# YuriPre2_0.net
KiCad netlist of a schematic drawn in EasyEDA Pro
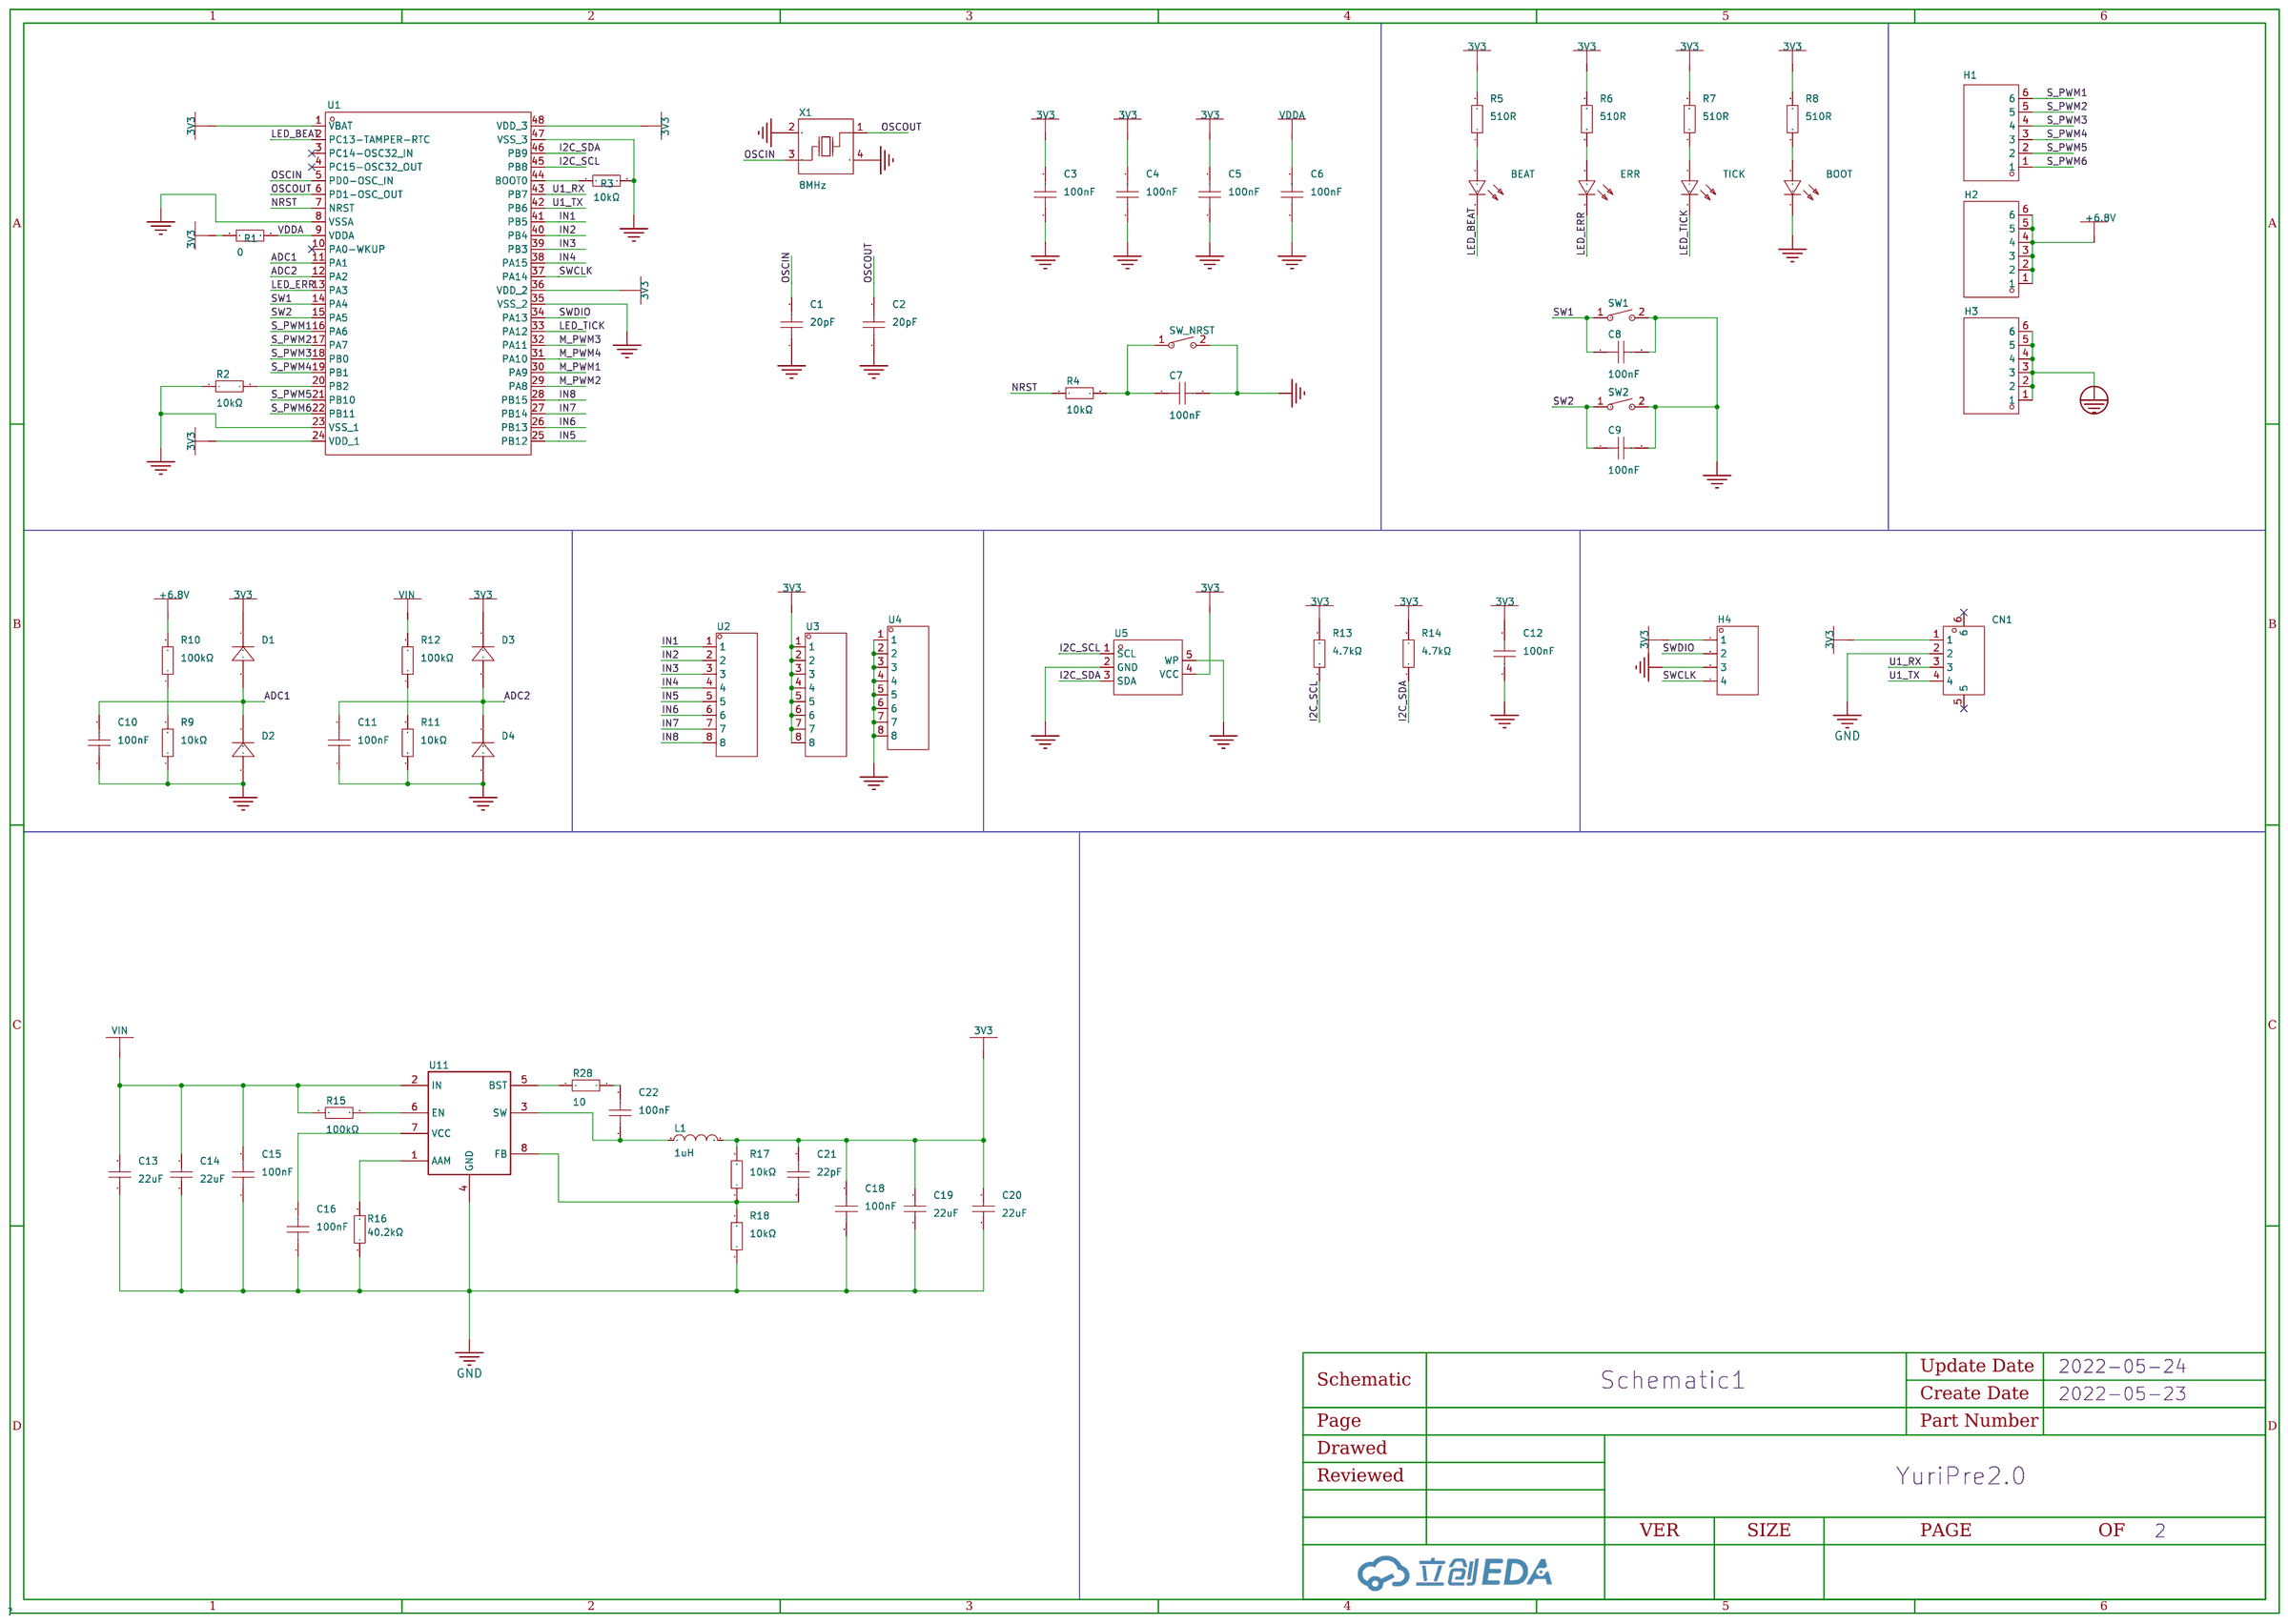
[diagram p0: P1]
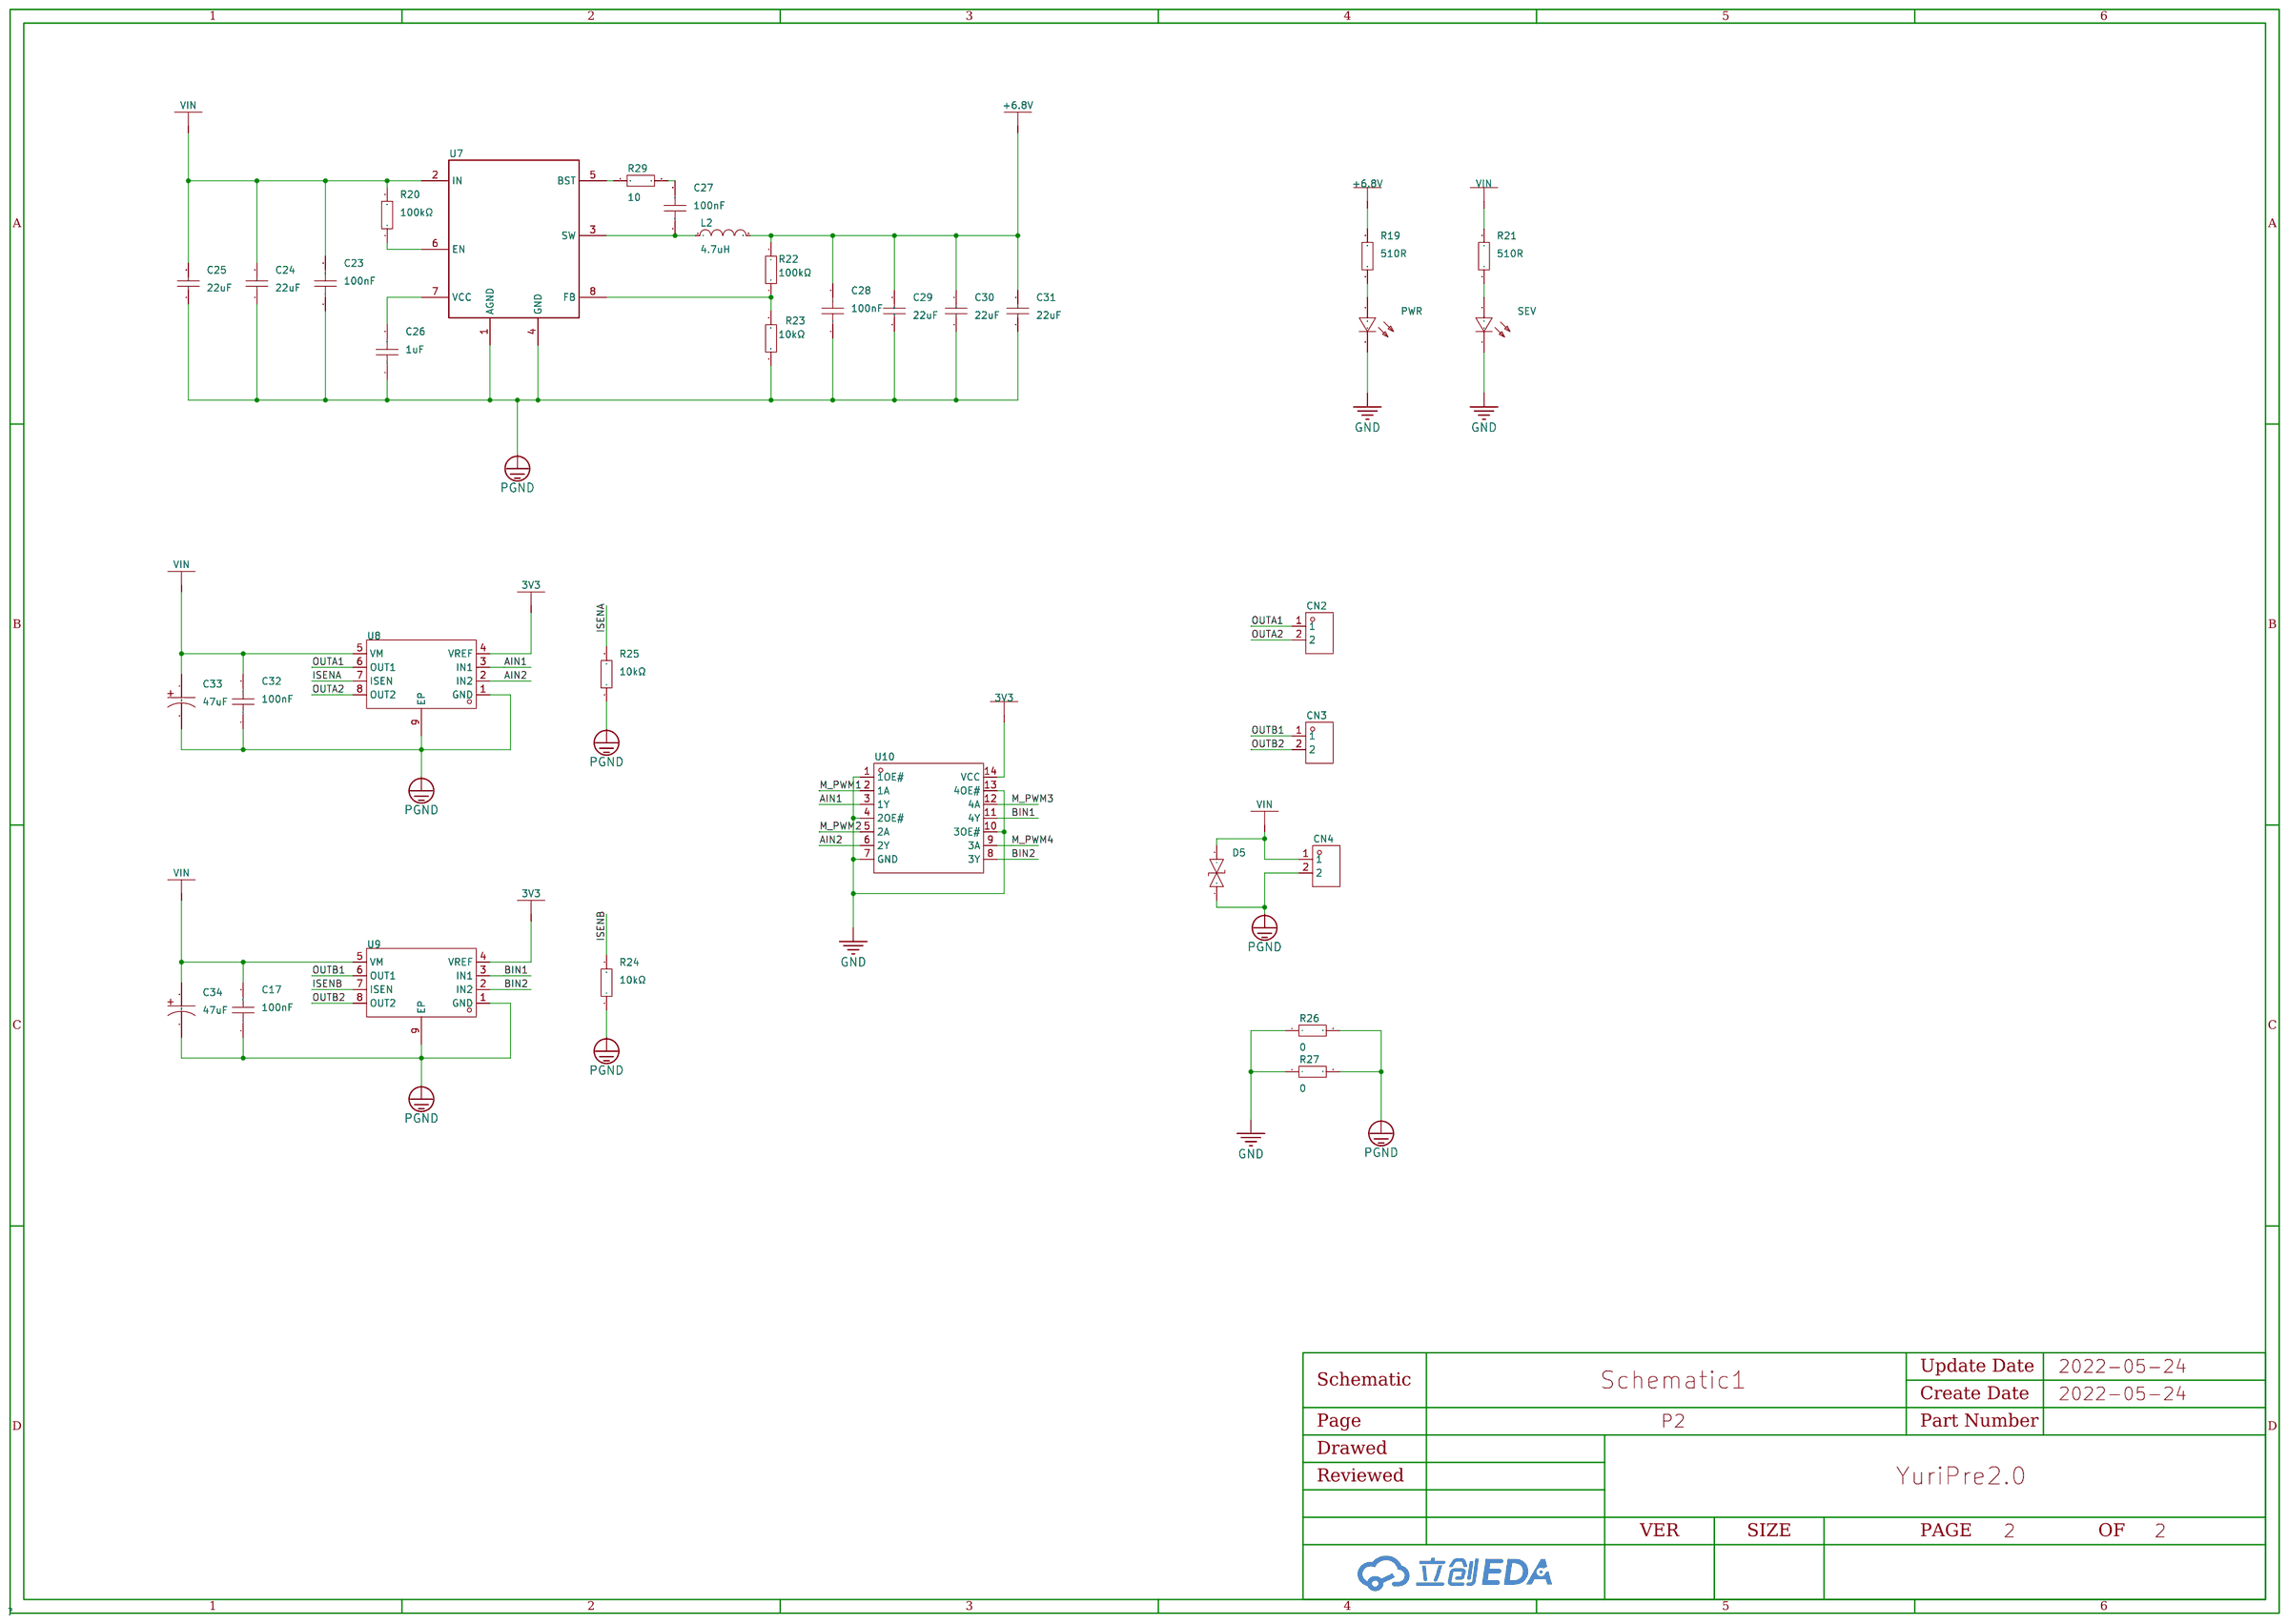
[diagram p1: P2]

(export (version "E")
  (design (tool "Eeschema 10.0.6"))
  (components
    (comp (ref "BEAT")
      (value "~")
      (footprint "easyedapro:LED0603-R-RD")
      (fields
        (field (name "Manufacturer Part") "19-217/GHC-YR1S2/3T")
        (field (name "Manufacturer") "EVERLIGHT(台湾亿光)")
      )
      (libsource (lib "easyedapro") (part "19-217/GHC-YR1S2/3T"))
    )
    (comp (ref "BOOT")
      (value "~")
      (footprint "easyedapro:LED0603-R-RD")
      (fields
        (field (name "Manufacturer Part") "19-217/GHC-YR1S2/3T")
        (field (name "Manufacturer") "EVERLIGHT(台湾亿光)")
      )
      (libsource (lib "easyedapro") (part "19-217/GHC-YR1S2/3T"))
    )
    (comp (ref "C1")
      (value "20pF")
      (footprint "easyedapro:C0402")
      (description "容值:100nF;精度:±10%;额定电压:25V;温度系数:X7R;")
      (fields (field (name "Manufacturer Part") "FN15X104K250PNG") (field (name "Manufacturer") "PSA(信昌电陶)"))
      (libsource (lib "easyedapro") (part "FN15X104K250PNG"))
    )
    (comp (ref "C2")
      (value "20pF")
      (footprint "easyedapro:C0402")
      (description "容值:100nF;精度:±10%;额定电压:25V;温度系数:X7R;")
      (fields (field (name "Manufacturer Part") "FN15X104K250PNG") (field (name "Manufacturer") "PSA(信昌电陶)"))
      (libsource (lib "easyedapro") (part "FN15X104K250PNG"))
    )
    (comp (ref "C3")
      (value "100nF")
      (footprint "easyedapro:C0402")
      (description "容值:100nF;精度:±10%;额定电压:25V;温度系数:X7R;")
      (fields (field (name "Manufacturer Part") "FN15X104K250PNG") (field (name "Manufacturer") "PSA(信昌电陶)"))
      (libsource (lib "easyedapro") (part "FN15X104K250PNG"))
    )
    (comp (ref "C4")
      (value "100nF")
      (footprint "easyedapro:C0402")
      (description "容值:100nF;精度:±10%;额定电压:25V;温度系数:X7R;")
      (fields (field (name "Manufacturer Part") "FN15X104K250PNG") (field (name "Manufacturer") "PSA(信昌电陶)"))
      (libsource (lib "easyedapro") (part "FN15X104K250PNG"))
    )
    (comp (ref "C5")
      (value "100nF")
      (footprint "easyedapro:C0402")
      (description "容值:100nF;精度:±10%;额定电压:25V;温度系数:X7R;")
      (fields (field (name "Manufacturer Part") "FN15X104K250PNG") (field (name "Manufacturer") "PSA(信昌电陶)"))
      (libsource (lib "easyedapro") (part "FN15X104K250PNG"))
    )
    (comp (ref "C6")
      (value "100nF")
      (footprint "easyedapro:C0402")
      (description "容值:100nF;精度:±10%;额定电压:25V;温度系数:X7R;")
      (fields (field (name "Manufacturer Part") "FN15X104K250PNG") (field (name "Manufacturer") "PSA(信昌电陶)"))
      (libsource (lib "easyedapro") (part "FN15X104K250PNG"))
    )
    (comp (ref "C7")
      (value "100nF")
      (footprint "easyedapro:C0402")
      (description "容值:100nF;精度:±10%;额定电压:25V;温度系数:X7R;")
      (fields (field (name "Manufacturer Part") "FN15X104K250PNG") (field (name "Manufacturer") "PSA(信昌电陶)"))
      (libsource (lib "easyedapro") (part "FN15X104K250PNG"))
    )
    (comp (ref "C8")
      (value "100nF")
      (footprint "easyedapro:C0402")
      (description "容值:100nF;精度:±10%;额定电压:25V;温度系数:X7R;")
      (fields (field (name "Manufacturer Part") "FN15X104K250PNG") (field (name "Manufacturer") "PSA(信昌电陶)"))
      (libsource (lib "easyedapro") (part "FN15X104K250PNG"))
    )
    (comp (ref "C9")
      (value "100nF")
      (footprint "easyedapro:C0402")
      (description "容值:100nF;精度:±10%;额定电压:25V;温度系数:X7R;")
      (fields (field (name "Manufacturer Part") "FN15X104K250PNG") (field (name "Manufacturer") "PSA(信昌电陶)"))
      (libsource (lib "easyedapro") (part "FN15X104K250PNG"))
    )
    (comp (ref "C10")
      (value "100nF")
      (footprint "easyedapro:C0402")
      (description "容值:100nF;精度:±10%;额定电压:25V;温度系数:X7R;")
      (fields (field (name "Manufacturer Part") "FN15X104K250PNG") (field (name "Manufacturer") "PSA(信昌电陶)"))
      (libsource (lib "easyedapro") (part "FN15X104K250PNG"))
    )
    (comp (ref "C11")
      (value "100nF")
      (footprint "easyedapro:C0402")
      (description "容值:100nF;精度:±10%;额定电压:25V;温度系数:X7R;")
      (fields (field (name "Manufacturer Part") "FN15X104K250PNG") (field (name "Manufacturer") "PSA(信昌电陶)"))
      (libsource (lib "easyedapro") (part "FN15X104K250PNG"))
    )
    (comp (ref "C12")
      (value "100nF")
      (footprint "easyedapro:C0402")
      (description "容值:100nF;精度:±10%;额定电压:25V;温度系数:X7R;")
      (fields (field (name "Manufacturer Part") "FN15X104K250PNG") (field (name "Manufacturer") "PSA(信昌电陶)"))
      (libsource (lib "easyedapro") (part "FN15X104K250PNG"))
    )
    (comp (ref "C13")
      (value "22uF")
      (footprint "easyedapro:C0805")
      (description "容值:100nF;精度:±10%;额定电压:50V;温度系数:X7R;")
      (fields
        (field (name "Manufacturer Part") "CC0805KRX7R9BB104")
        (field (name "Manufacturer") "YAGEO(国巨)")
      )
      (libsource (lib "easyedapro") (part "CC0805KRX7R9BB104"))
    )
    (comp (ref "C14")
      (value "22uF")
      (footprint "easyedapro:C0805")
      (description "容值:100nF;精度:±10%;额定电压:50V;温度系数:X7R;")
      (fields
        (field (name "Manufacturer Part") "CC0805KRX7R9BB104")
        (field (name "Manufacturer") "YAGEO(国巨)")
      )
      (libsource (lib "easyedapro") (part "CC0805KRX7R9BB104"))
    )
    (comp (ref "C15")
      (value "100nF")
      (footprint "easyedapro:C0603")
      (description "容值:100nF;精度:±10%;额定电压:50V;温度系数:X7R;")
      (fields
        (field (name "Manufacturer Part") "CC0603KRX7R9BB104")
        (field (name "Manufacturer") "YAGEO(国巨)")
      )
      (libsource (lib "easyedapro") (part "CC0603KRX7R9BB104"))
    )
    (comp (ref "C16")
      (value "100nF")
      (footprint "easyedapro:C0603")
      (description "容值:100nF;精度:±10%;额定电压:50V;温度系数:X7R;")
      (fields
        (field (name "Manufacturer Part") "CC0603KRX7R9BB104")
        (field (name "Manufacturer") "YAGEO(国巨)")
      )
      (libsource (lib "easyedapro") (part "CC0603KRX7R9BB104"))
    )
    (comp (ref "C18")
      (value "100nF")
      (footprint "easyedapro:C0603")
      (description "容值:100nF;精度:±10%;额定电压:50V;温度系数:X7R;")
      (fields
        (field (name "Manufacturer Part") "CC0603KRX7R9BB104")
        (field (name "Manufacturer") "YAGEO(国巨)")
      )
      (libsource (lib "easyedapro") (part "CC0603KRX7R9BB104"))
    )
    (comp (ref "C19")
      (value "22uF")
      (footprint "easyedapro:C0805")
      (description "容值:100nF;精度:±10%;额定电压:50V;温度系数:X7R;")
      (fields
        (field (name "Manufacturer Part") "CC0805KRX7R9BB104")
        (field (name "Manufacturer") "YAGEO(国巨)")
      )
      (libsource (lib "easyedapro") (part "CC0805KRX7R9BB104"))
    )
    (comp (ref "C20")
      (value "22uF")
      (footprint "easyedapro:C0805")
      (description "容值:100nF;精度:±10%;额定电压:50V;温度系数:X7R;")
      (fields
        (field (name "Manufacturer Part") "CC0805KRX7R9BB104")
        (field (name "Manufacturer") "YAGEO(国巨)")
      )
      (libsource (lib "easyedapro") (part "CC0805KRX7R9BB104"))
    )
    (comp (ref "C21")
      (value "22pF")
      (footprint "easyedapro:C0402")
      (description "容值:100nF;精度:±10%;额定电压:25V;温度系数:X7R;")
      (fields (field (name "Manufacturer Part") "FN15X104K250PNG") (field (name "Manufacturer") "PSA(信昌电陶)"))
      (libsource (lib "easyedapro") (part "FN15X104K250PNG"))
    )
    (comp (ref "C22")
      (value "100nF")
      (footprint "easyedapro:C0603")
      (description "容值:100nF;精度:±10%;额定电压:50V;温度系数:X7R;")
      (fields
        (field (name "Manufacturer Part") "CC0603KRX7R9BB104")
        (field (name "Manufacturer") "YAGEO(国巨)")
      )
      (libsource (lib "easyedapro") (part "CC0603KRX7R9BB104"))
    )
    (comp (ref "CN1")
      (value "~")
      (footprint "easyedapro:CONN-SMD_4P-1.25P_1.25T-4P")
      (description "参考系列:-;间距:1.25mm;插针结构:1x4P;排数:1;每排PIN数:4;行距:-;安装方式:-;触头材质:磷青铜;")
      (fields (field (name "Manufacturer Part") "1.25T-4P-WT") (field (name "Manufacturer") "韩国韩荣"))
      (libsource (lib "easyedapro") (part "1.25T-4P-WT"))
    )
    (comp (ref "D1")
      (value "~")
      (footprint "easyedapro:SOD-123FL_L2.6-W1.6-LS3.4-R-FD")
      (fields (field (name "Manufacturer Part") "1N4148W D1") (field (name "Manufacturer") "TC(德昌)"))
      (libsource (lib "easyedapro") (part "1N4148W-C129216"))
    )
    (comp (ref "D2")
      (value "~")
      (footprint "easyedapro:SOD-123FL_L2.6-W1.6-LS3.4-R-FD")
      (fields (field (name "Manufacturer Part") "1N4148W D1") (field (name "Manufacturer") "TC(德昌)"))
      (libsource (lib "easyedapro") (part "1N4148W-C129216"))
    )
    (comp (ref "D3")
      (value "~")
      (footprint "easyedapro:SOD-123FL_L2.6-W1.6-LS3.4-R-FD")
      (fields (field (name "Manufacturer Part") "1N4148W D1") (field (name "Manufacturer") "TC(德昌)"))
      (libsource (lib "easyedapro") (part "1N4148W-C129216"))
    )
    (comp (ref "D4")
      (value "~")
      (footprint "easyedapro:SOD-123FL_L2.6-W1.6-LS3.4-R-FD")
      (fields (field (name "Manufacturer Part") "1N4148W D1") (field (name "Manufacturer") "TC(德昌)"))
      (libsource (lib "easyedapro") (part "1N4148W-C129216"))
    )
    (comp (ref "ERR")
      (value "~")
      (footprint "easyedapro:LED0603-R-RD")
      (fields
        (field (name "Manufacturer Part") "19-217/GHC-YR1S2/3T")
        (field (name "Manufacturer") "EVERLIGHT(台湾亿光)")
      )
      (libsource (lib "easyedapro") (part "19-217/GHC-YR1S2/3T"))
    )
    (comp (ref "H1")
      (value "~")
      (footprint "easyedapro:HDR-TH_6P-P2.54-V_Z-211-0611-0021-001")
      (fields
        (field (name "Manufacturer Part") "Z-211-0611-0021-001")
        (field (name "Manufacturer") "Nextron(台湾正凌)")
      )
      (libsource (lib "easyedapro") (part "Z-211-0611-0021-001"))
    )
    (comp (ref "H2")
      (value "~")
      (footprint "easyedapro:HDR-TH_6P-P2.54-V_Z-211-0611-0021-001")
      (fields
        (field (name "Manufacturer Part") "Z-211-0611-0021-001")
        (field (name "Manufacturer") "Nextron(台湾正凌)")
      )
      (libsource (lib "easyedapro") (part "Z-211-0611-0021-001"))
    )
    (comp (ref "H3")
      (value "~")
      (footprint "easyedapro:HDR-TH_6P-P2.54-V_Z-211-0611-0021-001")
      (fields
        (field (name "Manufacturer Part") "Z-211-0611-0021-001")
        (field (name "Manufacturer") "Nextron(台湾正凌)")
      )
      (libsource (lib "easyedapro") (part "Z-211-0611-0021-001"))
    )
    (comp (ref "H4")
      (value "~")
      (footprint "easyedapro:HDR-TH_4P-P2.54-V-M")
      (fields (field (name "Manufacturer Part") "B-2100S04P-A110") (field (name "Manufacturer") "Ckmtw(灿科盟)"))
      (libsource (lib "easyedapro") (part "Header-Male-2.54_1x4"))
    )
    (comp (ref "L1")
      (value "1uH")
      (footprint "easyedapro:IND-SMD_L2.5-W2.0-1")
      (description "电感值:-;精度:-;额定电流:-;饱和电流(Isat):-;直流电阻(DCR):-;")
      (fields
        (field (name "Manufacturer Part") "MEKK2520T1R0M")
        (field (name "Manufacturer") "TAIYO YUDEN(太诱)")
      )
      (libsource (lib "easyedapro") (part "MEKK2520T1R0M"))
    )
    (comp (ref "R1")
      (value "0")
      (footprint "easyedapro:R0402")
      (description "电阻类型:薄膜电阻;阻值:10kΩ;精度:±0.5%;功率:63mW;温度系数:±25ppm/;最大工作电压:25V;工作温度范围:-55~+155;")
      (fields
        (field (name "Manufacturer Part") "TR0402D10K0Q1025Z")
        (field (name "Manufacturer") "EVER OHMS(天二科技)")
      )
      (libsource (lib "easyedapro") (part "TR0402D10KQ1025"))
    )
    (comp (ref "R2")
      (value "10kΩ")
      (footprint "easyedapro:R0402")
      (description "电阻类型:薄膜电阻;阻值:10kΩ;精度:±0.5%;功率:63mW;温度系数:±25ppm/;最大工作电压:25V;工作温度范围:-55~+155;")
      (fields
        (field (name "Manufacturer Part") "TR0402D10K0Q1025Z")
        (field (name "Manufacturer") "EVER OHMS(天二科技)")
      )
      (libsource (lib "easyedapro") (part "TR0402D10KQ1025"))
    )
    (comp (ref "R3")
      (value "10kΩ")
      (footprint "easyedapro:R0402")
      (description "电阻类型:薄膜电阻;阻值:10kΩ;精度:±0.5%;功率:63mW;温度系数:±25ppm/;最大工作电压:25V;工作温度范围:-55~+155;")
      (fields
        (field (name "Manufacturer Part") "TR0402D10K0Q1025Z")
        (field (name "Manufacturer") "EVER OHMS(天二科技)")
      )
      (libsource (lib "easyedapro") (part "TR0402D10KQ1025"))
    )
    (comp (ref "R4")
      (value "10kΩ")
      (footprint "easyedapro:R0402")
      (description "电阻类型:薄膜电阻;阻值:10kΩ;精度:±0.5%;功率:63mW;温度系数:±25ppm/;最大工作电压:25V;工作温度范围:-55~+155;")
      (fields
        (field (name "Manufacturer Part") "TR0402D10K0Q1025Z")
        (field (name "Manufacturer") "EVER OHMS(天二科技)")
      )
      (libsource (lib "easyedapro") (part "TR0402D10KQ1025"))
    )
    (comp (ref "R5")
      (value "510R")
      (footprint "easyedapro:R0402")
      (description "电阻类型:薄膜电阻;阻值:10kΩ;精度:±0.5%;功率:63mW;温度系数:±25ppm/;最大工作电压:25V;工作温度范围:-55~+155;")
      (fields
        (field (name "Manufacturer Part") "TR0402D10K0Q1025Z")
        (field (name "Manufacturer") "EVER OHMS(天二科技)")
      )
      (libsource (lib "easyedapro") (part "TR0402D10KQ1025"))
    )
    (comp (ref "R6")
      (value "510R")
      (footprint "easyedapro:R0402")
      (description "电阻类型:薄膜电阻;阻值:10kΩ;精度:±0.5%;功率:63mW;温度系数:±25ppm/;最大工作电压:25V;工作温度范围:-55~+155;")
      (fields
        (field (name "Manufacturer Part") "TR0402D10K0Q1025Z")
        (field (name "Manufacturer") "EVER OHMS(天二科技)")
      )
      (libsource (lib "easyedapro") (part "TR0402D10KQ1025"))
    )
    (comp (ref "R7")
      (value "510R")
      (footprint "easyedapro:R0402")
      (description "电阻类型:薄膜电阻;阻值:10kΩ;精度:±0.5%;功率:63mW;温度系数:±25ppm/;最大工作电压:25V;工作温度范围:-55~+155;")
      (fields
        (field (name "Manufacturer Part") "TR0402D10K0Q1025Z")
        (field (name "Manufacturer") "EVER OHMS(天二科技)")
      )
      (libsource (lib "easyedapro") (part "TR0402D10KQ1025"))
    )
    (comp (ref "R8")
      (value "510R")
      (footprint "easyedapro:R0402")
      (description "电阻类型:薄膜电阻;阻值:10kΩ;精度:±0.5%;功率:63mW;温度系数:±25ppm/;最大工作电压:25V;工作温度范围:-55~+155;")
      (fields
        (field (name "Manufacturer Part") "TR0402D10K0Q1025Z")
        (field (name "Manufacturer") "EVER OHMS(天二科技)")
      )
      (libsource (lib "easyedapro") (part "TR0402D10KQ1025"))
    )
    (comp (ref "R9")
      (value "10kΩ")
      (footprint "easyedapro:R0402")
      (description "电阻类型:薄膜电阻;阻值:10kΩ;精度:±0.5%;功率:63mW;温度系数:±25ppm/;最大工作电压:25V;工作温度范围:-55~+155;")
      (fields
        (field (name "Manufacturer Part") "TR0402D10K0Q1025Z")
        (field (name "Manufacturer") "EVER OHMS(天二科技)")
      )
      (libsource (lib "easyedapro") (part "TR0402D10KQ1025"))
    )
    (comp (ref "R10")
      (value "100kΩ")
      (footprint "easyedapro:R0402")
      (description "电阻类型:薄膜电阻;阻值:10kΩ;精度:±0.5%;功率:63mW;温度系数:±25ppm/;最大工作电压:25V;工作温度范围:-55~+155;")
      (fields
        (field (name "Manufacturer Part") "TR0402D10K0Q1025Z")
        (field (name "Manufacturer") "EVER OHMS(天二科技)")
      )
      (libsource (lib "easyedapro") (part "TR0402D10KQ1025"))
    )
    (comp (ref "R11")
      (value "10kΩ")
      (footprint "easyedapro:R0402")
      (description "电阻类型:薄膜电阻;阻值:10kΩ;精度:±0.5%;功率:63mW;温度系数:±25ppm/;最大工作电压:25V;工作温度范围:-55~+155;")
      (fields
        (field (name "Manufacturer Part") "TR0402D10K0Q1025Z")
        (field (name "Manufacturer") "EVER OHMS(天二科技)")
      )
      (libsource (lib "easyedapro") (part "TR0402D10KQ1025"))
    )
    (comp (ref "R12")
      (value "100kΩ")
      (footprint "easyedapro:R0402")
      (description "电阻类型:薄膜电阻;阻值:10kΩ;精度:±0.5%;功率:63mW;温度系数:±25ppm/;最大工作电压:25V;工作温度范围:-55~+155;")
      (fields
        (field (name "Manufacturer Part") "TR0402D10K0Q1025Z")
        (field (name "Manufacturer") "EVER OHMS(天二科技)")
      )
      (libsource (lib "easyedapro") (part "TR0402D10KQ1025"))
    )
    (comp (ref "R13")
      (value "4.7kΩ")
      (footprint "easyedapro:R0402")
      (description "电阻类型:薄膜电阻;阻值:10kΩ;精度:±0.5%;功率:63mW;温度系数:±25ppm/;最大工作电压:25V;工作温度范围:-55~+155;")
      (fields
        (field (name "Manufacturer Part") "TR0402D10K0Q1025Z")
        (field (name "Manufacturer") "EVER OHMS(天二科技)")
      )
      (libsource (lib "easyedapro") (part "TR0402D10KQ1025"))
    )
    (comp (ref "R14")
      (value "4.7kΩ")
      (footprint "easyedapro:R0402")
      (description "电阻类型:薄膜电阻;阻值:10kΩ;精度:±0.5%;功率:63mW;温度系数:±25ppm/;最大工作电压:25V;工作温度范围:-55~+155;")
      (fields
        (field (name "Manufacturer Part") "TR0402D10K0Q1025Z")
        (field (name "Manufacturer") "EVER OHMS(天二科技)")
      )
      (libsource (lib "easyedapro") (part "TR0402D10KQ1025"))
    )
    (comp (ref "R15")
      (value "100kΩ")
      (footprint "easyedapro:R0402")
      (description "电阻类型:薄膜电阻;阻值:10kΩ;精度:±0.5%;功率:63mW;温度系数:±25ppm/;最大工作电压:25V;工作温度范围:-55~+155;")
      (fields
        (field (name "Manufacturer Part") "TR0402D10K0Q1025Z")
        (field (name "Manufacturer") "EVER OHMS(天二科技)")
      )
      (libsource (lib "easyedapro") (part "TR0402D10KQ1025"))
    )
    (comp (ref "R16")
      (value "40.2kΩ")
      (footprint "easyedapro:R0402")
      (description "电阻类型:薄膜电阻;阻值:10kΩ;精度:±0.5%;功率:63mW;温度系数:±25ppm/;最大工作电压:25V;工作温度范围:-55~+155;")
      (fields
        (field (name "Manufacturer Part") "TR0402D10K0Q1025Z")
        (field (name "Manufacturer") "EVER OHMS(天二科技)")
      )
      (libsource (lib "easyedapro") (part "TR0402D10KQ1025"))
    )
    (comp (ref "R17")
      (value "10kΩ")
      (footprint "easyedapro:R0402")
      (description "电阻类型:薄膜电阻;阻值:10kΩ;精度:±0.5%;功率:63mW;温度系数:±25ppm/;最大工作电压:25V;工作温度范围:-55~+155;")
      (fields
        (field (name "Manufacturer Part") "TR0402D10K0Q1025Z")
        (field (name "Manufacturer") "EVER OHMS(天二科技)")
      )
      (libsource (lib "easyedapro") (part "TR0402D10KQ1025"))
    )
    (comp (ref "R18")
      (value "10kΩ")
      (footprint "easyedapro:R0402")
      (description "电阻类型:薄膜电阻;阻值:10kΩ;精度:±0.5%;功率:63mW;温度系数:±25ppm/;最大工作电压:25V;工作温度范围:-55~+155;")
      (fields
        (field (name "Manufacturer Part") "TR0402D10K0Q1025Z")
        (field (name "Manufacturer") "EVER OHMS(天二科技)")
      )
      (libsource (lib "easyedapro") (part "TR0402D10KQ1025"))
    )
    (comp (ref "R28")
      (value "10")
      (footprint "easyedapro:R0603")
      (description "电阻类型:薄膜电阻;阻值:10kΩ;精度:±0.1%;功率:100mW;温度系数:±25ppm/;最大工作电压:75V;工作温度范围:-55~+155;")
      (fields
        (field (name "Manufacturer Part") "TR0603B10K0P0525Z")
        (field (name "Manufacturer") "EVER OHMS(天二科技)")
      )
      (libsource (lib "easyedapro") (part "R_0603_EU"))
    )
    (comp (ref "SW1")
      (value "~")
      (footprint "easyedapro:SW-SMD_L4.0-W2.9-LS5.0")
      (fields (field (name "Manufacturer Part") "TS342A2P-WZ") (field (name "Manufacturer") "SHOU HAN(首韩)"))
      (libsource (lib "easyedapro") (part "TS342A2P-WZ"))
    )
    (comp (ref "SW2")
      (value "~")
      (footprint "easyedapro:SW-SMD_L4.0-W2.9-LS5.0")
      (fields (field (name "Manufacturer Part") "TS342A2P-WZ") (field (name "Manufacturer") "SHOU HAN(首韩)"))
      (libsource (lib "easyedapro") (part "TS342A2P-WZ"))
    )
    (comp (ref "SW_NRST")
      (value "~")
      (footprint "easyedapro:SW-SMD_L4.0-W2.9-LS5.0")
      (fields (field (name "Manufacturer Part") "TS342A2P-WZ") (field (name "Manufacturer") "SHOU HAN(首韩)"))
      (libsource (lib "easyedapro") (part "TS342A2P-WZ"))
    )
    (comp (ref "TICK")
      (value "~")
      (footprint "easyedapro:LED0603-R-RD")
      (fields
        (field (name "Manufacturer Part") "19-217/GHC-YR1S2/3T")
        (field (name "Manufacturer") "EVERLIGHT(台湾亿光)")
      )
      (libsource (lib "easyedapro") (part "19-217/GHC-YR1S2/3T"))
    )
    (comp (ref "U1")
      (value "~")
      (footprint "easyedapro:LQFP-48_L7.0-W7.0-P0.50-LS9.0-BL")
      (description "主频（MAX):72MHz;工作电压:2V ~ 3.6V;")
      (fields (field (name "Manufacturer Part") "STM32F103C8T6") (field (name "Manufacturer") "ST(意法半导体)"))
      (libsource (lib "easyedapro") (part "STM32F103C8T6"))
    )
    (comp (ref "U2")
      (value "~")
      (footprint "easyedapro:HDR-TH_8P-P2.54-V-M")
      (fields
        (field (name "Manufacturer Part") "Z-211-0811-0021-001")
        (field (name "Manufacturer") "Nextron(台湾正凌)")
      )
      (libsource (lib "easyedapro") (part "Z-211-0811-0021-001"))
    )
    (comp (ref "U3")
      (value "~")
      (footprint "easyedapro:HDR-TH_8P-P2.54-V-M")
      (fields
        (field (name "Manufacturer Part") "Z-211-0811-0021-001")
        (field (name "Manufacturer") "Nextron(台湾正凌)")
      )
      (libsource (lib "easyedapro") (part "Z-211-0811-0021-001"))
    )
    (comp (ref "U4")
      (value "~")
      (footprint "easyedapro:HDR-TH_8P-P2.54-V-M")
      (fields
        (field (name "Manufacturer Part") "Z-211-0811-0021-001")
        (field (name "Manufacturer") "Nextron(台湾正凌)")
      )
      (libsource (lib "easyedapro") (part "Z-211-0811-0021-001"))
    )
    (comp (ref "U5")
      (value "~")
      (footprint "easyedapro:SOT-23-5_L3.0-W1.7-P0.95-LS2.8-BL")
      (description "存储器类型:-;存储器容量:-;存储器接口类型:-;工作电压:-;")
      (fields (field (name "Manufacturer Part") "AT24C02M5/TR") (field (name "Manufacturer") "HGSEMI(华冠)"))
      (libsource (lib "easyedapro") (part "AT24C02M5/TR"))
    )
    (comp (ref "U11")
      (value "~")
      (footprint "easyedapro:TSOT23-8_L2.9-W1.6-P0.65-LS2.8-TL")
      (libsource (lib "easyedapro") (part "MP2318"))
    )
    (comp (ref "X1")
      (value "8MHz")
      (footprint "easyedapro:CRYSTAL-SMD_4P-L3.2-W2.5-BL")
      (description "晶振类型:贴片无源晶振;频率:12MHz;频率公差:±10ppm;频率稳定度:±30ppm;负载电容:10pF;工作温度:-40~+85;")
      (fields (field (name "Manufacturer Part") "X322512MMB4SI") (field (name "Manufacturer") "YXC扬兴科技"))
      (libsource (lib "easyedapro") (part "X322512MMB4SI"))
    )
    (comp (ref "C17")
      (value "100nF")
      (footprint "easyedapro:C0603")
      (description "容值:100nF;精度:±10%;额定电压:50V;温度系数:X7R;")
      (fields
        (field (name "Manufacturer Part") "CC0603KRX7R9BB104")
        (field (name "Manufacturer") "YAGEO(国巨)")
      )
      (libsource (lib "easyedapro") (part "CC0603KRX7R9BB104"))
    )
    (comp (ref "C23")
      (value "100nF")
      (footprint "easyedapro:C0603")
      (description "容值:100nF;精度:±10%;额定电压:50V;温度系数:X7R;")
      (fields
        (field (name "Manufacturer Part") "CC0603KRX7R9BB104")
        (field (name "Manufacturer") "YAGEO(国巨)")
      )
      (libsource (lib "easyedapro") (part "CC0603KRX7R9BB104"))
    )
    (comp (ref "C24")
      (value "22uF")
      (footprint "easyedapro:C0805")
      (description "容值:100nF;精度:±10%;额定电压:50V;温度系数:X7R;")
      (fields
        (field (name "Manufacturer Part") "CC0805KRX7R9BB104")
        (field (name "Manufacturer") "YAGEO(国巨)")
      )
      (libsource (lib "easyedapro") (part "CC0805KRX7R9BB104"))
    )
    (comp (ref "C25")
      (value "22uF")
      (footprint "easyedapro:C0805")
      (description "容值:100nF;精度:±10%;额定电压:50V;温度系数:X7R;")
      (fields
        (field (name "Manufacturer Part") "CC0805KRX7R9BB104")
        (field (name "Manufacturer") "YAGEO(国巨)")
      )
      (libsource (lib "easyedapro") (part "CC0805KRX7R9BB104"))
    )
    (comp (ref "C26")
      (value "1uF")
      (footprint "easyedapro:C0603")
      (description "容值:100nF;精度:±10%;额定电压:50V;温度系数:X7R;")
      (fields
        (field (name "Manufacturer Part") "CC0603KRX7R9BB104")
        (field (name "Manufacturer") "YAGEO(国巨)")
      )
      (libsource (lib "easyedapro") (part "CC0603KRX7R9BB104"))
    )
    (comp (ref "C27")
      (value "100nF")
      (footprint "easyedapro:C0603")
      (description "容值:100nF;精度:±10%;额定电压:50V;温度系数:X7R;")
      (fields
        (field (name "Manufacturer Part") "CC0603KRX7R9BB104")
        (field (name "Manufacturer") "YAGEO(国巨)")
      )
      (libsource (lib "easyedapro") (part "CC0603KRX7R9BB104"))
    )
    (comp (ref "C28")
      (value "100nF")
      (footprint "easyedapro:C0603")
      (description "容值:100nF;精度:±10%;额定电压:50V;温度系数:X7R;")
      (fields
        (field (name "Manufacturer Part") "CC0603KRX7R9BB104")
        (field (name "Manufacturer") "YAGEO(国巨)")
      )
      (libsource (lib "easyedapro") (part "CC0603KRX7R9BB104"))
    )
    (comp (ref "C29")
      (value "22uF")
      (footprint "easyedapro:C0805")
      (description "容值:100nF;精度:±10%;额定电压:50V;温度系数:X7R;")
      (fields
        (field (name "Manufacturer Part") "CC0805KRX7R9BB104")
        (field (name "Manufacturer") "YAGEO(国巨)")
      )
      (libsource (lib "easyedapro") (part "CC0805KRX7R9BB104"))
    )
    (comp (ref "C30")
      (value "22uF")
      (footprint "easyedapro:C0805")
      (description "容值:100nF;精度:±10%;额定电压:50V;温度系数:X7R;")
      (fields
        (field (name "Manufacturer Part") "CC0805KRX7R9BB104")
        (field (name "Manufacturer") "YAGEO(国巨)")
      )
      (libsource (lib "easyedapro") (part "CC0805KRX7R9BB104"))
    )
    (comp (ref "C31")
      (value "22uF")
      (footprint "easyedapro:C0805")
      (description "容值:100nF;精度:±10%;额定电压:50V;温度系数:X7R;")
      (fields
        (field (name "Manufacturer Part") "CC0805KRX7R9BB104")
        (field (name "Manufacturer") "YAGEO(国巨)")
      )
      (libsource (lib "easyedapro") (part "CC0805KRX7R9BB104"))
    )
    (comp (ref "C32")
      (value "100nF")
      (footprint "easyedapro:C0603")
      (description "容值:100nF;精度:±10%;额定电压:50V;温度系数:X7R;")
      (fields
        (field (name "Manufacturer Part") "CC0603KRX7R9BB104")
        (field (name "Manufacturer") "YAGEO(国巨)")
      )
      (libsource (lib "easyedapro") (part "CC0603KRX7R9BB104"))
    )
    (comp (ref "C33")
      (value "47uF")
      (footprint "easyedapro:CAP-TH_BD5.0-P2.00-D0.8-FD")
      (fields
        (field (name "Manufacturer Part") "SHL25VB47M5*11_LO")
        (field (name "Manufacturer") "SAMYOUNG(韩国三莹)")
      )
      (libsource (lib "easyedapro") (part "SHL25VB47M5*11_LO"))
    )
    (comp (ref "C34")
      (value "47uF")
      (footprint "easyedapro:CAP-TH_BD5.0-P2.00-D0.8-FD")
      (fields
        (field (name "Manufacturer Part") "SHL25VB47M5*11_LO")
        (field (name "Manufacturer") "SAMYOUNG(韩国三莹)")
      )
      (libsource (lib "easyedapro") (part "SHL25VB47M5*11_LO"))
    )
    (comp (ref "CN2")
      (value "~")
      (footprint "easyedapro:CONN-TH_OQ0232510000G")
      (fields (field (name "Manufacturer Part") "OQ0232510000G") (field (name "Manufacturer") "Amphenol"))
      (libsource (lib "easyedapro") (part "OQ0232510000G"))
    )
    (comp (ref "CN3")
      (value "~")
      (footprint "easyedapro:CONN-TH_OQ0232510000G")
      (fields (field (name "Manufacturer Part") "OQ0232510000G") (field (name "Manufacturer") "Amphenol"))
      (libsource (lib "easyedapro") (part "OQ0232510000G"))
    )
    (comp (ref "CN4")
      (value "~")
      (footprint "easyedapro:CONN-TH_OQ0232510000G")
      (fields (field (name "Manufacturer Part") "OQ0232510000G") (field (name "Manufacturer") "Amphenol"))
      (libsource (lib "easyedapro") (part "OQ0232510000G"))
    )
    (comp (ref "D5")
      (value "~")
      (footprint "easyedapro:SOD-123_L2.8-W1.8-LS3.7-BI")
      (fields (field (name "Manufacturer Part") "SMF18CA") (field (name "Manufacturer") "FMS(台湾美丽微)"))
      (libsource (lib "easyedapro") (part "SMF18CA_C188308"))
    )
    (comp (ref "L2")
      (value "4.7uH")
      (footprint "easyedapro:IND-SMD_L5.7-W5.4")
      (description "电感值:4.7uH;精度:±20%;额定电流:-;直流电阻(DCR):-;")
      (fields
        (field (name "Manufacturer Part") "MHCI05030-4R7M-R8LM")
        (field (name "Manufacturer") "chilisin(奇力新)")
      )
      (libsource (lib "easyedapro") (part "MHCI05030-4R7M-R8LM"))
    )
    (comp (ref "PWR")
      (value "~")
      (footprint "easyedapro:LED0603-R-RD")
      (fields
        (field (name "Manufacturer Part") "19-217/GHC-YR1S2/3T")
        (field (name "Manufacturer") "EVERLIGHT(台湾亿光)")
      )
      (libsource (lib "easyedapro") (part "19-217/GHC-YR1S2/3T"))
    )
    (comp (ref "R19")
      (value "510R")
      (footprint "easyedapro:R0402")
      (description "电阻类型:薄膜电阻;阻值:10kΩ;精度:±0.5%;功率:63mW;温度系数:±25ppm/;最大工作电压:25V;工作温度范围:-55~+155;")
      (fields
        (field (name "Manufacturer Part") "TR0402D10K0Q1025Z")
        (field (name "Manufacturer") "EVER OHMS(天二科技)")
      )
      (libsource (lib "easyedapro") (part "TR0402D10KQ1025"))
    )
    (comp (ref "R20")
      (value "100kΩ")
      (footprint "easyedapro:R0402")
      (description "电阻类型:薄膜电阻;阻值:10kΩ;精度:±0.5%;功率:63mW;温度系数:±25ppm/;最大工作电压:25V;工作温度范围:-55~+155;")
      (fields
        (field (name "Manufacturer Part") "TR0402D10K0Q1025Z")
        (field (name "Manufacturer") "EVER OHMS(天二科技)")
      )
      (libsource (lib "easyedapro") (part "TR0402D10KQ1025"))
    )
    (comp (ref "R21")
      (value "510R")
      (footprint "easyedapro:R0402")
      (description "电阻类型:薄膜电阻;阻值:10kΩ;精度:±0.5%;功率:63mW;温度系数:±25ppm/;最大工作电压:25V;工作温度范围:-55~+155;")
      (fields
        (field (name "Manufacturer Part") "TR0402D10K0Q1025Z")
        (field (name "Manufacturer") "EVER OHMS(天二科技)")
      )
      (libsource (lib "easyedapro") (part "TR0402D10KQ1025"))
    )
    (comp (ref "R22")
      (value "100kΩ")
      (footprint "easyedapro:R0402")
      (description "电阻类型:薄膜电阻;阻值:10kΩ;精度:±0.5%;功率:63mW;温度系数:±25ppm/;最大工作电压:25V;工作温度范围:-55~+155;")
      (fields
        (field (name "Manufacturer Part") "TR0402D10K0Q1025Z")
        (field (name "Manufacturer") "EVER OHMS(天二科技)")
      )
      (libsource (lib "easyedapro") (part "TR0402D10KQ1025"))
    )
    (comp (ref "R23")
      (value "10kΩ")
      (footprint "easyedapro:R0402")
      (description "电阻类型:薄膜电阻;阻值:10kΩ;精度:±0.5%;功率:63mW;温度系数:±25ppm/;最大工作电压:25V;工作温度范围:-55~+155;")
      (fields
        (field (name "Manufacturer Part") "TR0402D10K0Q1025Z")
        (field (name "Manufacturer") "EVER OHMS(天二科技)")
      )
      (libsource (lib "easyedapro") (part "TR0402D10KQ1025"))
    )
    (comp (ref "R24")
      (value "10kΩ")
      (footprint "easyedapro:R0603")
      (description "电阻类型:薄膜电阻;阻值:10kΩ;精度:±0.1%;功率:100mW;温度系数:±25ppm/;最大工作电压:75V;工作温度范围:-55~+155;")
      (fields
        (field (name "Manufacturer Part") "TR0603B10K0P0525Z")
        (field (name "Manufacturer") "EVER OHMS(天二科技)")
      )
      (libsource (lib "easyedapro") (part "R_0603_EU"))
    )
    (comp (ref "R25")
      (value "10kΩ")
      (footprint "easyedapro:R0603")
      (description "电阻类型:薄膜电阻;阻值:10kΩ;精度:±0.1%;功率:100mW;温度系数:±25ppm/;最大工作电压:75V;工作温度范围:-55~+155;")
      (fields
        (field (name "Manufacturer Part") "TR0603B10K0P0525Z")
        (field (name "Manufacturer") "EVER OHMS(天二科技)")
      )
      (libsource (lib "easyedapro") (part "R_0603_EU"))
    )
    (comp (ref "R26")
      (value "0")
      (footprint "easyedapro:R0603")
      (description "电阻类型:薄膜电阻;阻值:10kΩ;精度:±0.1%;功率:100mW;温度系数:±25ppm/;最大工作电压:75V;工作温度范围:-55~+155;")
      (fields
        (field (name "Manufacturer Part") "TR0603B10K0P0525Z")
        (field (name "Manufacturer") "EVER OHMS(天二科技)")
      )
      (libsource (lib "easyedapro") (part "R_0603_EU"))
    )
    (comp (ref "R27")
      (value "0")
      (footprint "easyedapro:R0603")
      (description "电阻类型:薄膜电阻;阻值:10kΩ;精度:±0.1%;功率:100mW;温度系数:±25ppm/;最大工作电压:75V;工作温度范围:-55~+155;")
      (fields
        (field (name "Manufacturer Part") "TR0603B10K0P0525Z")
        (field (name "Manufacturer") "EVER OHMS(天二科技)")
      )
      (libsource (lib "easyedapro") (part "R_0603_EU"))
    )
    (comp (ref "R29")
      (value "10")
      (footprint "easyedapro:R0603")
      (description "电阻类型:薄膜电阻;阻值:10kΩ;精度:±0.1%;功率:100mW;温度系数:±25ppm/;最大工作电压:75V;工作温度范围:-55~+155;")
      (fields
        (field (name "Manufacturer Part") "TR0603B10K0P0525Z")
        (field (name "Manufacturer") "EVER OHMS(天二科技)")
      )
      (libsource (lib "easyedapro") (part "R_0603_EU"))
    )
    (comp (ref "SEV")
      (value "~")
      (footprint "easyedapro:LED0603-R-RD")
      (fields
        (field (name "Manufacturer Part") "19-217/GHC-YR1S2/3T")
        (field (name "Manufacturer") "EVERLIGHT(台湾亿光)")
      )
      (libsource (lib "easyedapro") (part "19-217/GHC-YR1S2/3T"))
    )
    (comp (ref "U7")
      (value "~")
      (footprint "easyedapro:TSOT23-8_L2.9-W1.6-P0.65-LS2.8-TL")
      (libsource (lib "easyedapro") (part "MP2236"))
    )
    (comp (ref "U8")
      (value "~")
      (footprint "easyedapro:SOP-8_L4.9-W3.9-P1.27-LS6.0-BL-EP")
      (description "直流电机驱动器, 3.6A峰值驱动输出,2A持续输出能力")
      (fields (field (name "Manufacturer Part") "AT8870") (field (name "Manufacturer") "嘉兴禾润"))
      (libsource (lib "easyedapro") (part "AT8870"))
    )
    (comp (ref "U9")
      (value "~")
      (footprint "easyedapro:SOP-8_L4.9-W3.9-P1.27-LS6.0-BL-EP")
      (description "直流电机驱动器, 3.6A峰值驱动输出,2A持续输出能力")
      (fields (field (name "Manufacturer Part") "AT8870") (field (name "Manufacturer") "嘉兴禾润"))
      (libsource (lib "easyedapro") (part "AT8870"))
    )
    (comp (ref "U10")
      (value "~")
      (footprint "easyedapro:TSSOP-14_L5.0-W4.4-P0.65-LS6.5-BL")
      (description "逻辑电路的归属系列:74HC;逻辑类型:缓冲器，非反向;元件数:4;每元件位数:1;")
      (fields (field (name "Manufacturer Part") "SN74HC125PWR") (field (name "Manufacturer") "TI(德州仪器)"))
      (libsource (lib "easyedapro") (part "SN74HC125PWR"))
    )
  )
  (nets
    (net (code "1") (name "+6.8V") (class "Default")
      (node (ref "C28") (pin "2") (pinfunction "2_2") (pintype "input"))
      (node (ref "C29") (pin "2") (pinfunction "2_2") (pintype "input"))
      (node (ref "C30") (pin "2") (pinfunction "2_2") (pintype "input"))
      (node (ref "C31") (pin "2") (pinfunction "2_2") (pintype "input"))
      (node (ref "H2") (pin "1") (pinfunction "1_1") (pintype "input"))
      (node (ref "H2") (pin "2") (pinfunction "2_2") (pintype "input"))
      (node (ref "H2") (pin "3") (pinfunction "3_3") (pintype "input"))
      (node (ref "H2") (pin "4") (pinfunction "4_4") (pintype "input"))
      (node (ref "H2") (pin "5") (pinfunction "5_5") (pintype "input"))
      (node (ref "H2") (pin "6") (pinfunction "6_6") (pintype "input"))
      (node (ref "L2") (pin "2") (pinfunction "2_2") (pintype "input"))
      (node (ref "R10") (pin "2") (pinfunction "2_2") (pintype "input"))
      (node (ref "R19") (pin "2") (pinfunction "2_2") (pintype "input"))
      (node (ref "R22") (pin "2") (pinfunction "2_2") (pintype "input"))
    )
    (net (code "2") (name "3V3") (class "Default")
      (node (ref "C12") (pin "2") (pinfunction "2_2") (pintype "input"))
      (node (ref "C18") (pin "2") (pinfunction "2_2") (pintype "input"))
      (node (ref "C19") (pin "2") (pinfunction "2_2") (pintype "input"))
      (node (ref "C20") (pin "2") (pinfunction "2_2") (pintype "input"))
      (node (ref "C21") (pin "2") (pinfunction "2_2") (pintype "input"))
      (node (ref "C3") (pin "2") (pinfunction "2_2") (pintype "input"))
      (node (ref "C4") (pin "2") (pinfunction "2_2") (pintype "input"))
      (node (ref "C5") (pin "2") (pinfunction "2_2") (pintype "input"))
      (node (ref "CN1") (pin "1") (pinfunction "1_1") (pintype "input"))
      (node (ref "D1") (pin "1") (pinfunction "C_1") (pintype "input"))
      (node (ref "D3") (pin "1") (pinfunction "C_1") (pintype "input"))
      (node (ref "H4") (pin "1") (pinfunction "1_1") (pintype "input"))
      (node (ref "L1") (pin "2") (pinfunction "2_2") (pintype "input"))
      (node (ref "R1") (pin "1") (pinfunction "1_1") (pintype "input"))
      (node (ref "R13") (pin "2") (pinfunction "2_2") (pintype "input"))
      (node (ref "R14") (pin "2") (pinfunction "2_2") (pintype "input"))
      (node (ref "R17") (pin "2") (pinfunction "2_2") (pintype "input"))
      (node (ref "R5") (pin "2") (pinfunction "2_2") (pintype "input"))
      (node (ref "R6") (pin "2") (pinfunction "2_2") (pintype "input"))
      (node (ref "R7") (pin "2") (pinfunction "2_2") (pintype "input"))
      (node (ref "R8") (pin "2") (pinfunction "2_2") (pintype "input"))
      (node (ref "U1") (pin "1") (pinfunction "VBAT_1") (pintype "input"))
      (node (ref "U1") (pin "24") (pinfunction "VDD_1_24") (pintype "input"))
      (node (ref "U1") (pin "36") (pinfunction "VDD_2_36") (pintype "input"))
      (node (ref "U1") (pin "48") (pinfunction "VDD_3_48") (pintype "input"))
      (node (ref "U10") (pin "14") (pinfunction "VCC_14") (pintype "input"))
      (node (ref "U3") (pin "1") (pinfunction "1_1") (pintype "input"))
      (node (ref "U3") (pin "2") (pinfunction "2_2") (pintype "input"))
      (node (ref "U3") (pin "3") (pinfunction "3_3") (pintype "input"))
      (node (ref "U3") (pin "4") (pinfunction "4_4") (pintype "input"))
      (node (ref "U3") (pin "5") (pinfunction "5_5") (pintype "input"))
      (node (ref "U3") (pin "6") (pinfunction "6_6") (pintype "input"))
      (node (ref "U3") (pin "7") (pinfunction "7_7") (pintype "input"))
      (node (ref "U3") (pin "8") (pinfunction "8_8") (pintype "input"))
      (node (ref "U5") (pin "4") (pinfunction "VCC_4") (pintype "input"))
      (node (ref "U8") (pin "4") (pinfunction "VREF_4") (pintype "input"))
      (node (ref "U9") (pin "4") (pinfunction "VREF_4") (pintype "input"))
    )
    (net (code "3") (name "ADC1") (class "Default")
      (node (ref "C10") (pin "2") (pinfunction "2_2") (pintype "input"))
      (node (ref "D1") (pin "2") (pinfunction "A_2") (pintype "input"))
      (node (ref "D2") (pin "1") (pinfunction "C_1") (pintype "input"))
      (node (ref "U1") (pin "11") (pinfunction "PA1_11") (pintype "input"))
    )
    (net (code "4") (name "ADC2") (class "Default")
      (node (ref "C11") (pin "2") (pinfunction "2_2") (pintype "input"))
      (node (ref "D3") (pin "2") (pinfunction "A_2") (pintype "input"))
      (node (ref "D4") (pin "1") (pinfunction "C_1") (pintype "input"))
      (node (ref "U1") (pin "12") (pinfunction "PA2_12") (pintype "input"))
    )
    (net (code "5") (name "AIN1") (class "Default")
      (node (ref "U10") (pin "3") (pinfunction "1Y_3") (pintype "input"))
      (node (ref "U8") (pin "3") (pinfunction "IN1_3") (pintype "input"))
    )
    (net (code "6") (name "AIN2") (class "Default")
      (node (ref "U10") (pin "6") (pinfunction "2Y_6") (pintype "input"))
      (node (ref "U8") (pin "2") (pinfunction "IN2_2") (pintype "input"))
    )
    (net (code "7") (name "BIN1") (class "Default")
      (node (ref "U10") (pin "11") (pinfunction "4Y_11") (pintype "input"))
      (node (ref "U9") (pin "3") (pinfunction "IN1_3") (pintype "input"))
    )
    (net (code "8") (name "BIN2") (class "Default")
      (node (ref "U10") (pin "8") (pinfunction "3Y_8") (pintype "input"))
      (node (ref "U9") (pin "2") (pinfunction "IN2_2") (pintype "input"))
    )
    (net (code "9") (name "GND") (class "Default")
      (node (ref "BOOT") (pin "2") (pinfunction "C_2") (pintype "input"))
      (node (ref "C1") (pin "1") (pinfunction "1_1") (pintype "input"))
      (node (ref "C10") (pin "1") (pinfunction "1_1") (pintype "input"))
      (node (ref "C11") (pin "1") (pinfunction "1_1") (pintype "input"))
      (node (ref "C12") (pin "1") (pinfunction "1_1") (pintype "input"))
      (node (ref "C13") (pin "1") (pinfunction "1_1") (pintype "input"))
      (node (ref "C14") (pin "1") (pinfunction "1_1") (pintype "input"))
      (node (ref "C15") (pin "1") (pinfunction "1_1") (pintype "input"))
      (node (ref "C16") (pin "1") (pinfunction "1_1") (pintype "input"))
      (node (ref "C18") (pin "1") (pinfunction "1_1") (pintype "input"))
      (node (ref "C19") (pin "1") (pinfunction "1_1") (pintype "input"))
      (node (ref "C2") (pin "1") (pinfunction "1_1") (pintype "input"))
      (node (ref "C20") (pin "1") (pinfunction "1_1") (pintype "input"))
      (node (ref "C3") (pin "1") (pinfunction "1_1") (pintype "input"))
      (node (ref "C4") (pin "1") (pinfunction "1_1") (pintype "input"))
      (node (ref "C5") (pin "1") (pinfunction "1_1") (pintype "input"))
      (node (ref "C6") (pin "1") (pinfunction "1_1") (pintype "input"))
      (node (ref "C7") (pin "2") (pinfunction "2_2") (pintype "input"))
      (node (ref "C8") (pin "2") (pinfunction "2_2") (pintype "input"))
      (node (ref "C9") (pin "2") (pinfunction "2_2") (pintype "input"))
      (node (ref "CN1") (pin "2") (pinfunction "2_2") (pintype "input"))
      (node (ref "D2") (pin "2") (pinfunction "A_2") (pintype "input"))
      (node (ref "D4") (pin "2") (pinfunction "A_2") (pintype "input"))
      (node (ref "H4") (pin "3") (pinfunction "3_3") (pintype "input"))
      (node (ref "PWR") (pin "2") (pinfunction "C_2") (pintype "input"))
      (node (ref "R11") (pin "1") (pinfunction "1_1") (pintype "input"))
      (node (ref "R16") (pin "1") (pinfunction "1_1") (pintype "input"))
      (node (ref "R18") (pin "1") (pinfunction "1_1") (pintype "input"))
      (node (ref "R2") (pin "1") (pinfunction "1_1") (pintype "input"))
      (node (ref "R26") (pin "1") (pinfunction "1_1") (pintype "input"))
      (node (ref "R27") (pin "1") (pinfunction "1_1") (pintype "input"))
      (node (ref "R3") (pin "2") (pinfunction "2_2") (pintype "input"))
      (node (ref "R9") (pin "1") (pinfunction "1_1") (pintype "input"))
      (node (ref "SEV") (pin "2") (pinfunction "C_2") (pintype "input"))
      (node (ref "SW1") (pin "2") (pinfunction "2_2") (pintype "input"))
      (node (ref "SW2") (pin "2") (pinfunction "2_2") (pintype "input"))
      (node (ref "SW_NRST") (pin "2") (pinfunction "2_2") (pintype "input"))
      (node (ref "U1") (pin "23") (pinfunction "VSS_1_23") (pintype "input"))
      (node (ref "U1") (pin "35") (pinfunction "VSS_2_35") (pintype "input"))
      (node (ref "U1") (pin "47") (pinfunction "VSS_3_47") (pintype "input"))
      (node (ref "U1") (pin "8") (pinfunction "VSSA_8") (pintype "input"))
      (node (ref "U10") (pin "1") (pinfunction "1OE#_1") (pintype "input"))
      (node (ref "U10") (pin "10") (pinfunction "3OE#_10") (pintype "input"))
      (node (ref "U10") (pin "13") (pinfunction "4OE#_13") (pintype "input"))
      (node (ref "U10") (pin "4") (pinfunction "2OE#_4") (pintype "input"))
      (node (ref "U10") (pin "7") (pinfunction "GND_7") (pintype "input"))
      (node (ref "U11") (pin "4") (pinfunction "GND_4") (pintype "input"))
      (node (ref "U4") (pin "1") (pinfunction "1_1") (pintype "input"))
      (node (ref "U4") (pin "2") (pinfunction "2_2") (pintype "input"))
      (node (ref "U4") (pin "3") (pinfunction "3_3") (pintype "input"))
      (node (ref "U4") (pin "4") (pinfunction "4_4") (pintype "input"))
      (node (ref "U4") (pin "5") (pinfunction "5_5") (pintype "input"))
      (node (ref "U4") (pin "6") (pinfunction "6_6") (pintype "input"))
      (node (ref "U4") (pin "7") (pinfunction "7_7") (pintype "input"))
      (node (ref "U4") (pin "8") (pinfunction "8_8") (pintype "input"))
      (node (ref "U5") (pin "2") (pinfunction "GND_2") (pintype "input"))
      (node (ref "U5") (pin "5") (pinfunction "WP_5") (pintype "input"))
      (node (ref "X1") (pin "2") (pinfunction "GND_2") (pintype "input"))
      (node (ref "X1") (pin "4") (pinfunction "GND_4") (pintype "input"))
    )
    (net (code "10") (name "I2C_SCL") (class "Default")
      (node (ref "R13") (pin "1") (pinfunction "1_1") (pintype "input"))
      (node (ref "U1") (pin "45") (pinfunction "PB8_45") (pintype "input"))
      (node (ref "U5") (pin "1") (pinfunction "SCL_1") (pintype "input"))
    )
    (net (code "11") (name "I2C_SDA") (class "Default")
      (node (ref "R14") (pin "1") (pinfunction "1_1") (pintype "input"))
      (node (ref "U1") (pin "46") (pinfunction "PB9_46") (pintype "input"))
      (node (ref "U5") (pin "3") (pinfunction "SDA_3") (pintype "input"))
    )
    (net (code "12") (name "IN1") (class "Default")
      (node (ref "U1") (pin "41") (pinfunction "PB5_41") (pintype "input"))
      (node (ref "U2") (pin "1") (pinfunction "1_1") (pintype "input"))
    )
    (net (code "13") (name "IN2") (class "Default")
      (node (ref "U1") (pin "40") (pinfunction "PB4_40") (pintype "input"))
      (node (ref "U2") (pin "2") (pinfunction "2_2") (pintype "input"))
    )
    (net (code "14") (name "IN3") (class "Default")
      (node (ref "U1") (pin "39") (pinfunction "PB3_39") (pintype "input"))
      (node (ref "U2") (pin "3") (pinfunction "3_3") (pintype "input"))
    )
    (net (code "15") (name "IN4") (class "Default")
      (node (ref "U1") (pin "38") (pinfunction "PA15_38") (pintype "input"))
      (node (ref "U2") (pin "4") (pinfunction "4_4") (pintype "input"))
    )
    (net (code "16") (name "IN5") (class "Default")
      (node (ref "U1") (pin "25") (pinfunction "PB12_25") (pintype "input"))
      (node (ref "U2") (pin "5") (pinfunction "5_5") (pintype "input"))
    )
    (net (code "17") (name "IN6") (class "Default")
      (node (ref "U1") (pin "26") (pinfunction "PB13_26") (pintype "input"))
      (node (ref "U2") (pin "6") (pinfunction "6_6") (pintype "input"))
    )
    (net (code "18") (name "IN7") (class "Default")
      (node (ref "U1") (pin "27") (pinfunction "PB14_27") (pintype "input"))
      (node (ref "U2") (pin "7") (pinfunction "7_7") (pintype "input"))
    )
    (net (code "19") (name "IN8") (class "Default")
      (node (ref "U1") (pin "28") (pinfunction "PB15_28") (pintype "input"))
      (node (ref "U2") (pin "8") (pinfunction "8_8") (pintype "input"))
    )
    (net (code "20") (name "ISENA") (class "Default")
      (node (ref "R25") (pin "2") (pinfunction "2_2") (pintype "input"))
      (node (ref "U8") (pin "7") (pinfunction "ISEN_7") (pintype "input"))
    )
    (net (code "21") (name "ISENB") (class "Default")
      (node (ref "R24") (pin "2") (pinfunction "2_2") (pintype "input"))
      (node (ref "U9") (pin "7") (pinfunction "ISEN_7") (pintype "input"))
    )
    (net (code "22") (name "LED_BEAT") (class "Default")
      (node (ref "BEAT") (pin "2") (pinfunction "C_2") (pintype "input"))
      (node (ref "U1") (pin "2") (pinfunction "PC13-TAMPER-RTC_2") (pintype "input"))
    )
    (net (code "23") (name "LED_ERR") (class "Default")
      (node (ref "ERR") (pin "2") (pinfunction "C_2") (pintype "input"))
      (node (ref "U1") (pin "13") (pinfunction "PA3_13") (pintype "input"))
    )
    (net (code "24") (name "LED_TICK") (class "Default")
      (node (ref "TICK") (pin "2") (pinfunction "C_2") (pintype "input"))
      (node (ref "U1") (pin "33") (pinfunction "PA12_33") (pintype "input"))
    )
    (net (code "25") (name "M_PWM1") (class "Default")
      (node (ref "U1") (pin "30") (pinfunction "PA9_30") (pintype "input"))
      (node (ref "U10") (pin "2") (pinfunction "1A_2") (pintype "input"))
    )
    (net (code "26") (name "M_PWM2") (class "Default")
      (node (ref "U1") (pin "29") (pinfunction "PA8_29") (pintype "input"))
      (node (ref "U10") (pin "5") (pinfunction "2A_5") (pintype "input"))
    )
    (net (code "27") (name "M_PWM3") (class "Default")
      (node (ref "U1") (pin "32") (pinfunction "PA11_32") (pintype "input"))
      (node (ref "U10") (pin "12") (pinfunction "4A_12") (pintype "input"))
    )
    (net (code "28") (name "M_PWM4") (class "Default")
      (node (ref "U1") (pin "31") (pinfunction "PA10_31") (pintype "input"))
      (node (ref "U10") (pin "9") (pinfunction "3A_9") (pintype "input"))
    )
    (net (code "29") (name "NRST") (class "Default")
      (node (ref "R4") (pin "1") (pinfunction "1_1") (pintype "input"))
      (node (ref "U1") (pin "7") (pinfunction "NRST_7") (pintype "input"))
    )
    (net (code "30") (name "Net-(BEAT-A)") (class "Default")
      (node (ref "BEAT") (pin "1") (pinfunction "A_1") (pintype "input"))
      (node (ref "R5") (pin "1") (pinfunction "1_1") (pintype "input"))
    )
    (net (code "31") (name "Net-(BOOT-A)") (class "Default")
      (node (ref "BOOT") (pin "1") (pinfunction "A_1") (pintype "input"))
      (node (ref "R8") (pin "1") (pinfunction "1_1") (pintype "input"))
    )
    (net (code "32") (name "Net-(C7-Pad1)") (class "Default")
      (node (ref "C7") (pin "1") (pinfunction "1_1") (pintype "input"))
      (node (ref "R4") (pin "2") (pinfunction "2_2") (pintype "input"))
      (node (ref "SW_NRST") (pin "1") (pinfunction "1_1") (pintype "input"))
    )
    (net (code "33") (name "Net-(C22-Pad2)") (class "Default")
      (node (ref "C22") (pin "2") (pinfunction "2_2") (pintype "input"))
      (node (ref "R28") (pin "2") (pinfunction "2_2") (pintype "input"))
    )
    (net (code "34") (name "Net-(C27-Pad2)") (class "Default")
      (node (ref "C27") (pin "2") (pinfunction "2_2") (pintype "input"))
      (node (ref "R29") (pin "2") (pinfunction "2_2") (pintype "input"))
    )
    (net (code "35") (name "Net-(ERR-A)") (class "Default")
      (node (ref "ERR") (pin "1") (pinfunction "A_1") (pintype "input"))
      (node (ref "R6") (pin "1") (pinfunction "1_1") (pintype "input"))
    )
    (net (code "36") (name "Net-(PWR-A)") (class "Default")
      (node (ref "PWR") (pin "1") (pinfunction "A_1") (pintype "input"))
      (node (ref "R19") (pin "1") (pinfunction "1_1") (pintype "input"))
    )
    (net (code "37") (name "Net-(R10-Pad1)") (class "Default")
      (node (ref "R10") (pin "1") (pinfunction "1_1") (pintype "input"))
      (node (ref "R9") (pin "2") (pinfunction "2_2") (pintype "input"))
    )
    (net (code "38") (name "Net-(R11-Pad2)") (class "Default")
      (node (ref "R11") (pin "2") (pinfunction "2_2") (pintype "input"))
      (node (ref "R12") (pin "1") (pinfunction "1_1") (pintype "input"))
    )
    (net (code "39") (name "Net-(SEV-A)") (class "Default")
      (node (ref "R21") (pin "1") (pinfunction "1_1") (pintype "input"))
      (node (ref "SEV") (pin "1") (pinfunction "A_1") (pintype "input"))
    )
    (net (code "40") (name "Net-(TICK-A)") (class "Default")
      (node (ref "R7") (pin "1") (pinfunction "1_1") (pintype "input"))
      (node (ref "TICK") (pin "1") (pinfunction "A_1") (pintype "input"))
    )
    (net (code "41") (name "Net-(U1-BOOT0)") (class "Default")
      (node (ref "R3") (pin "1") (pinfunction "1_1") (pintype "input"))
      (node (ref "U1") (pin "44") (pinfunction "BOOT0_44") (pintype "input"))
    )
    (net (code "42") (name "Net-(U1-PB2)") (class "Default")
      (node (ref "R2") (pin "2") (pinfunction "2_2") (pintype "input"))
      (node (ref "U1") (pin "20") (pinfunction "PB2_20") (pintype "input"))
    )
    (net (code "43") (name "Net-(U7-BST)") (class "Default")
      (node (ref "R29") (pin "1") (pinfunction "1_1") (pintype "input"))
      (node (ref "U7") (pin "5") (pinfunction "BST_5") (pintype "input"))
    )
    (net (code "44") (name "Net-(U7-EN)") (class "Default")
      (node (ref "R20") (pin "1") (pinfunction "1_1") (pintype "input"))
      (node (ref "U7") (pin "6") (pinfunction "EN_6") (pintype "input"))
    )
    (net (code "45") (name "Net-(U7-FB)") (class "Default")
      (node (ref "R22") (pin "1") (pinfunction "1_1") (pintype "input"))
      (node (ref "R23") (pin "2") (pinfunction "2_2") (pintype "input"))
      (node (ref "U7") (pin "8") (pinfunction "FB_8") (pintype "input"))
    )
    (net (code "46") (name "Net-(U7-SW)") (class "Default")
      (node (ref "C27") (pin "1") (pinfunction "1_1") (pintype "input"))
      (node (ref "L2") (pin "1") (pinfunction "1_1") (pintype "input"))
      (node (ref "U7") (pin "3") (pinfunction "SW_3") (pintype "input"))
    )
    (net (code "47") (name "Net-(U7-VCC)") (class "Default")
      (node (ref "C26") (pin "2") (pinfunction "2_2") (pintype "input"))
      (node (ref "U7") (pin "7") (pinfunction "VCC_7") (pintype "input"))
    )
    (net (code "48") (name "Net-(U11-AAM)") (class "Default")
      (node (ref "R16") (pin "2") (pinfunction "2_2") (pintype "input"))
      (node (ref "U11") (pin "1") (pinfunction "AAM_1") (pintype "input"))
    )
    (net (code "49") (name "Net-(U11-BST)") (class "Default")
      (node (ref "R28") (pin "1") (pinfunction "1_1") (pintype "input"))
      (node (ref "U11") (pin "5") (pinfunction "BST_5") (pintype "input"))
    )
    (net (code "50") (name "Net-(U11-EN)") (class "Default")
      (node (ref "R15") (pin "2") (pinfunction "2_2") (pintype "input"))
      (node (ref "U11") (pin "6") (pinfunction "EN_6") (pintype "input"))
    )
    (net (code "51") (name "Net-(U11-FB)") (class "Default")
      (node (ref "C21") (pin "1") (pinfunction "1_1") (pintype "input"))
      (node (ref "R17") (pin "1") (pinfunction "1_1") (pintype "input"))
      (node (ref "R18") (pin "2") (pinfunction "2_2") (pintype "input"))
      (node (ref "U11") (pin "8") (pinfunction "FB_8") (pintype "input"))
    )
    (net (code "52") (name "Net-(U11-SW)") (class "Default")
      (node (ref "C22") (pin "1") (pinfunction "1_1") (pintype "input"))
      (node (ref "L1") (pin "1") (pinfunction "1_1") (pintype "input"))
      (node (ref "U11") (pin "3") (pinfunction "SW_3") (pintype "input"))
    )
    (net (code "53") (name "Net-(U11-VCC)") (class "Default")
      (node (ref "C16") (pin "2") (pinfunction "2_2") (pintype "input"))
      (node (ref "U11") (pin "7") (pinfunction "VCC_7") (pintype "input"))
    )
    (net (code "54") (name "OSCIN") (class "Default")
      (node (ref "C1") (pin "2") (pinfunction "2_2") (pintype "input"))
      (node (ref "U1") (pin "5") (pinfunction "PD0-OSC_IN_5") (pintype "input"))
      (node (ref "X1") (pin "3") (pinfunction "OSC2_3") (pintype "input"))
    )
    (net (code "55") (name "OSCOUT") (class "Default")
      (node (ref "C2") (pin "2") (pinfunction "2_2") (pintype "input"))
      (node (ref "U1") (pin "6") (pinfunction "PD1-OSC_OUT_6") (pintype "input"))
      (node (ref "X1") (pin "1") (pinfunction "OSC1_1") (pintype "input"))
    )
    (net (code "56") (name "OUTA1") (class "Default")
      (node (ref "CN2") (pin "1") (pinfunction "1_1") (pintype "input"))
      (node (ref "U8") (pin "6") (pinfunction "OUT1_6") (pintype "input"))
    )
    (net (code "57") (name "OUTA2") (class "Default")
      (node (ref "CN2") (pin "2") (pinfunction "2_2") (pintype "input"))
      (node (ref "U8") (pin "8") (pinfunction "OUT2_8") (pintype "input"))
    )
    (net (code "58") (name "OUTB1") (class "Default")
      (node (ref "CN3") (pin "1") (pinfunction "1_1") (pintype "input"))
      (node (ref "U9") (pin "6") (pinfunction "OUT1_6") (pintype "input"))
    )
    (net (code "59") (name "OUTB2") (class "Default")
      (node (ref "CN3") (pin "2") (pinfunction "2_2") (pintype "input"))
      (node (ref "U9") (pin "8") (pinfunction "OUT2_8") (pintype "input"))
    )
    (net (code "60") (name "PGND") (class "Default")
      (node (ref "C17") (pin "1") (pinfunction "1_1") (pintype "input"))
      (node (ref "C23") (pin "1") (pinfunction "1_1") (pintype "input"))
      (node (ref "C24") (pin "1") (pinfunction "1_1") (pintype "input"))
      (node (ref "C25") (pin "1") (pinfunction "1_1") (pintype "input"))
      (node (ref "C26") (pin "1") (pinfunction "1_1") (pintype "input"))
      (node (ref "C28") (pin "1") (pinfunction "1_1") (pintype "input"))
      (node (ref "C29") (pin "1") (pinfunction "1_1") (pintype "input"))
      (node (ref "C30") (pin "1") (pinfunction "1_1") (pintype "input"))
      (node (ref "C31") (pin "1") (pinfunction "1_1") (pintype "input"))
      (node (ref "C32") (pin "1") (pinfunction "1_1") (pintype "input"))
      (node (ref "C33") (pin "2") (pinfunction "2_2") (pintype "input"))
      (node (ref "C34") (pin "2") (pinfunction "2_2") (pintype "input"))
      (node (ref "CN4") (pin "2") (pinfunction "2_2") (pintype "input"))
      (node (ref "D5") (pin "1") (pinfunction "K_1") (pintype "input"))
      (node (ref "H3") (pin "1") (pinfunction "1_1") (pintype "input"))
      (node (ref "H3") (pin "2") (pinfunction "2_2") (pintype "input"))
      (node (ref "H3") (pin "3") (pinfunction "3_3") (pintype "input"))
      (node (ref "H3") (pin "4") (pinfunction "4_4") (pintype "input"))
      (node (ref "H3") (pin "5") (pinfunction "5_5") (pintype "input"))
      (node (ref "H3") (pin "6") (pinfunction "6_6") (pintype "input"))
      (node (ref "R23") (pin "1") (pinfunction "1_1") (pintype "input"))
      (node (ref "R24") (pin "1") (pinfunction "1_1") (pintype "input"))
      (node (ref "R25") (pin "1") (pinfunction "1_1") (pintype "input"))
      (node (ref "R26") (pin "2") (pinfunction "2_2") (pintype "input"))
      (node (ref "R27") (pin "2") (pinfunction "2_2") (pintype "input"))
      (node (ref "U7") (pin "1") (pinfunction "AGND_1") (pintype "input"))
      (node (ref "U7") (pin "4") (pinfunction "GND_4") (pintype "input"))
      (node (ref "U8") (pin "1") (pinfunction "GND_1") (pintype "input"))
      (node (ref "U8") (pin "9") (pinfunction "EP_9") (pintype "input"))
      (node (ref "U9") (pin "1") (pinfunction "GND_1") (pintype "input"))
      (node (ref "U9") (pin "9") (pinfunction "EP_9") (pintype "input"))
    )
    (net (code "61") (name "SW1") (class "Default")
      (node (ref "C8") (pin "1") (pinfunction "1_1") (pintype "input"))
      (node (ref "SW1") (pin "1") (pinfunction "1_1") (pintype "input"))
      (node (ref "U1") (pin "14") (pinfunction "PA4_14") (pintype "input"))
    )
    (net (code "62") (name "SW2") (class "Default")
      (node (ref "C9") (pin "1") (pinfunction "1_1") (pintype "input"))
      (node (ref "SW2") (pin "1") (pinfunction "1_1") (pintype "input"))
      (node (ref "U1") (pin "15") (pinfunction "PA5_15") (pintype "input"))
    )
    (net (code "63") (name "SWCLK") (class "Default")
      (node (ref "H4") (pin "4") (pinfunction "4_4") (pintype "input"))
      (node (ref "U1") (pin "37") (pinfunction "PA14_37") (pintype "input"))
    )
    (net (code "64") (name "SWDIO") (class "Default")
      (node (ref "H4") (pin "2") (pinfunction "2_2") (pintype "input"))
      (node (ref "U1") (pin "34") (pinfunction "PA13_34") (pintype "input"))
    )
    (net (code "65") (name "S_PWM1") (class "Default")
      (node (ref "H1") (pin "6") (pinfunction "6_6") (pintype "input"))
      (node (ref "U1") (pin "16") (pinfunction "PA6_16") (pintype "input"))
    )
    (net (code "66") (name "S_PWM2") (class "Default")
      (node (ref "H1") (pin "5") (pinfunction "5_5") (pintype "input"))
      (node (ref "U1") (pin "17") (pinfunction "PA7_17") (pintype "input"))
    )
    (net (code "67") (name "S_PWM3") (class "Default")
      (node (ref "H1") (pin "4") (pinfunction "4_4") (pintype "input"))
      (node (ref "U1") (pin "18") (pinfunction "PB0_18") (pintype "input"))
    )
    (net (code "68") (name "S_PWM4") (class "Default")
      (node (ref "H1") (pin "3") (pinfunction "3_3") (pintype "input"))
      (node (ref "U1") (pin "19") (pinfunction "PB1_19") (pintype "input"))
    )
    (net (code "69") (name "S_PWM5") (class "Default")
      (node (ref "H1") (pin "2") (pinfunction "2_2") (pintype "input"))
      (node (ref "U1") (pin "21") (pinfunction "PB10_21") (pintype "input"))
    )
    (net (code "70") (name "S_PWM6") (class "Default")
      (node (ref "H1") (pin "1") (pinfunction "1_1") (pintype "input"))
      (node (ref "U1") (pin "22") (pinfunction "PB11_22") (pintype "input"))
    )
    (net (code "71") (name "U1_RX") (class "Default")
      (node (ref "CN1") (pin "3") (pinfunction "3_3") (pintype "input"))
      (node (ref "U1") (pin "43") (pinfunction "PB7_43") (pintype "input"))
    )
    (net (code "72") (name "U1_TX") (class "Default")
      (node (ref "CN1") (pin "4") (pinfunction "4_4") (pintype "input"))
      (node (ref "U1") (pin "42") (pinfunction "PB6_42") (pintype "input"))
    )
    (net (code "73") (name "VDDA") (class "Default")
      (node (ref "C6") (pin "2") (pinfunction "2_2") (pintype "input"))
      (node (ref "R1") (pin "2") (pinfunction "2_2") (pintype "input"))
      (node (ref "U1") (pin "9") (pinfunction "VDDA_9") (pintype "input"))
    )
    (net (code "74") (name "VIN") (class "Default")
      (node (ref "C13") (pin "2") (pinfunction "2_2") (pintype "input"))
      (node (ref "C14") (pin "2") (pinfunction "2_2") (pintype "input"))
      (node (ref "C15") (pin "2") (pinfunction "2_2") (pintype "input"))
      (node (ref "C17") (pin "2") (pinfunction "2_2") (pintype "input"))
      (node (ref "C23") (pin "2") (pinfunction "2_2") (pintype "input"))
      (node (ref "C24") (pin "2") (pinfunction "2_2") (pintype "input"))
      (node (ref "C25") (pin "2") (pinfunction "2_2") (pintype "input"))
      (node (ref "C32") (pin "2") (pinfunction "2_2") (pintype "input"))
      (node (ref "C33") (pin "1") (pinfunction "1_1") (pintype "input"))
      (node (ref "C34") (pin "1") (pinfunction "1_1") (pintype "input"))
      (node (ref "CN4") (pin "1") (pinfunction "1_1") (pintype "input"))
      (node (ref "D5") (pin "2") (pinfunction "A_2") (pintype "input"))
      (node (ref "R12") (pin "2") (pinfunction "2_2") (pintype "input"))
      (node (ref "R15") (pin "1") (pinfunction "1_1") (pintype "input"))
      (node (ref "R20") (pin "2") (pinfunction "2_2") (pintype "input"))
      (node (ref "R21") (pin "2") (pinfunction "2_2") (pintype "input"))
      (node (ref "U11") (pin "2") (pinfunction "IN_2") (pintype "input"))
      (node (ref "U7") (pin "2") (pinfunction "IN_2") (pintype "input"))
      (node (ref "U8") (pin "5") (pinfunction "VM_5") (pintype "input"))
      (node (ref "U9") (pin "5") (pinfunction "VM_5") (pintype "input"))
    )
    (net (code "75") (name "unconnected-(CN1-Pad5)") (class "Default")
      (node (ref "CN1") (pin "5") (pinfunction "5_5") (pintype "input+no_connect"))
    )
    (net (code "76") (name "unconnected-(CN1-Pad6)") (class "Default")
      (node (ref "CN1") (pin "6") (pinfunction "6_6") (pintype "input+no_connect"))
    )
    (net (code "77") (name "unconnected-(U1-PA0-WKUP-Pad10)") (class "Default")
      (node (ref "U1") (pin "10") (pinfunction "PA0-WKUP_10") (pintype "input+no_connect"))
    )
    (net (code "78") (name "unconnected-(U1-PC14-OSC32_IN-Pad3)") (class "Default")
      (node (ref "U1") (pin "3") (pinfunction "PC14-OSC32_IN_3") (pintype "input+no_connect"))
    )
    (net (code "79") (name "unconnected-(U1-PC15-OSC32_OUT-Pad4)") (class "Default")
      (node (ref "U1") (pin "4") (pinfunction "PC15-OSC32_OUT_4") (pintype "input+no_connect"))
    )
  )
)
